# SimpleCircuit.net
KiCad netlist of a schematic drawn in EAGLE
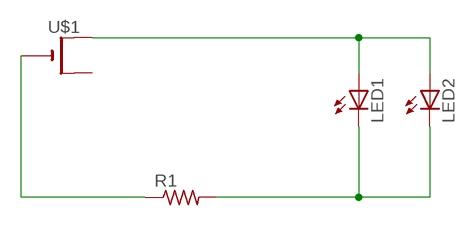
[diagram p0: schematic, sheet 1]

(export (version "E")
  (design (tool "Eeschema 10.0.6"))
  (components
    (comp (ref "LED1")
      (value "LED5MM")
      (footprint "eagle-import:LED5MM")
      (libsource (lib "eagle-import") (part "LED5MM"))
    )
    (comp (ref "LED2")
      (value "LED5MM")
      (footprint "eagle-import:LED5MM")
      (libsource (lib "eagle-import") (part "LED5MM"))
    )
    (comp (ref "R1")
      (value "R-US_0309/12")
      (footprint "eagle-import:0309_12")
      (libsource (lib "eagle-import") (part "R-US_0309/12"))
    )
    (comp (ref "U$1")
      (value "CR2032THM")
      (footprint "eagle-import:CR2032-THRU")
      (libsource (lib "eagle-import") (part "CR2032THM"))
    )
  )
  (nets
    (net (code "1") (name "Net-(LED1-C)") (class "Default")
      (node (ref "LED1") (pin "K") (pinfunction "C_K") (pintype "passive"))
      (node (ref "LED2") (pin "K") (pinfunction "C_K") (pintype "passive"))
      (node (ref "R1") (pin "2") (pinfunction "2_2") (pintype "passive"))
    )
    (net (code "2") (name "Net-(R1-Pad1)") (class "Default")
      (node (ref "R1") (pin "1") (pinfunction "1_1") (pintype "passive"))
      (node (ref "U$1") (pin "-") (pinfunction "-_-") (pintype "passive"))
    )
    (net (code "3") (name "Net-(U$1-+)") (class "Default")
      (node (ref "LED1") (pin "A") (pinfunction "A_A") (pintype "passive"))
      (node (ref "LED2") (pin "A") (pinfunction "A_A") (pintype "passive"))
      (node (ref "U$1") (pin "+1") (pinfunction "+_+1") (pintype "passive"))
    )
    (net (code "4") (name "unconnected-(U$1-+1-Pad+2)") (class "Default")
      (node (ref "U$1") (pin "+2") (pinfunction "+1_+2") (pintype "passive"))
    )
  )
)
